# ble.net
KiCad netlist of a schematic drawn in EAGLE
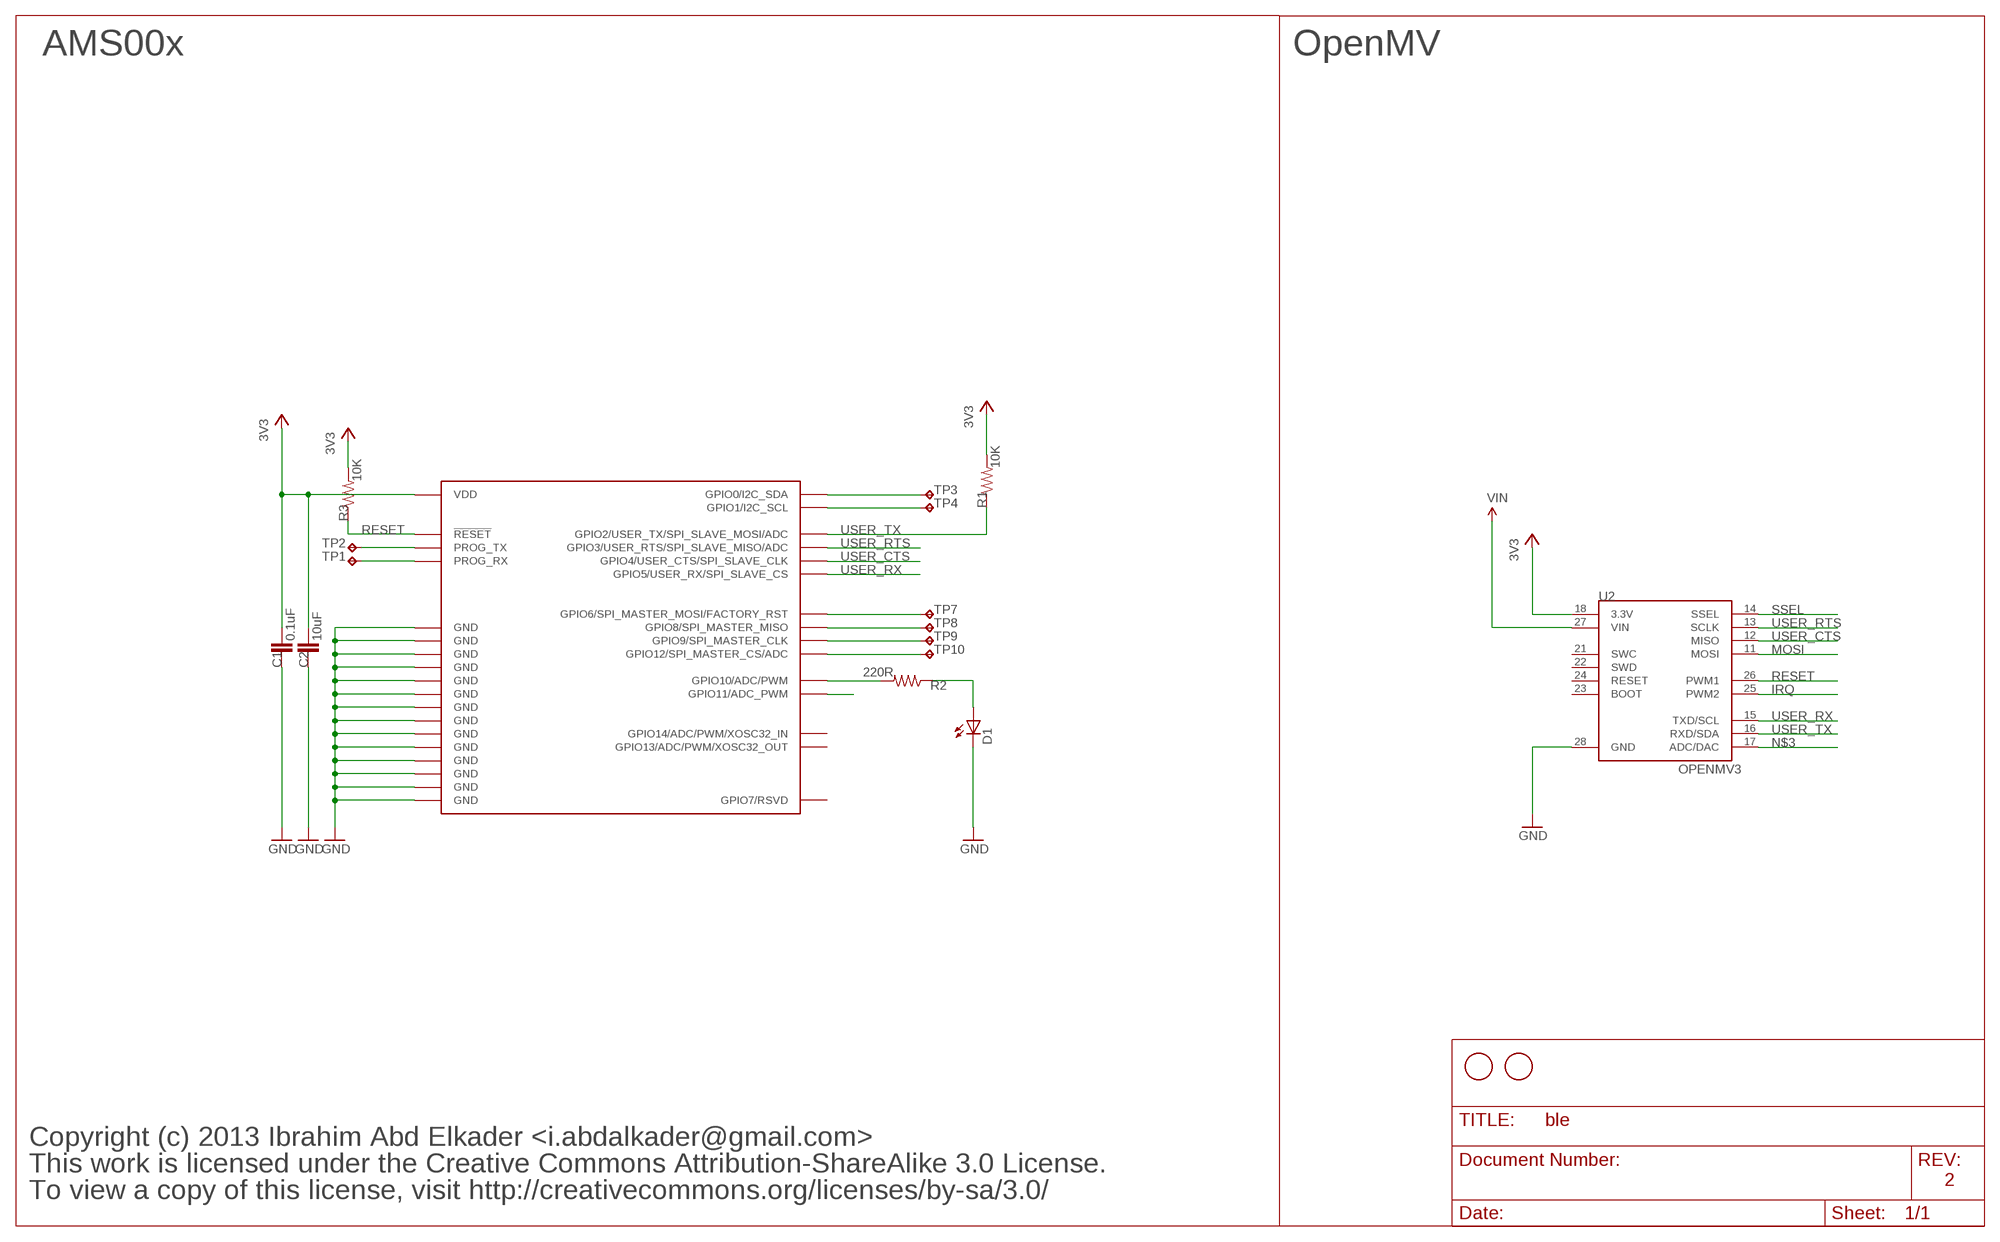
[diagram p0: schematic, sheet 1]

(export (version "E")
  (design (tool "Eeschema 10.0.6"))
  (components
    (comp (ref "C1")
      (value "0.1uF")
      (footprint "eagle-import:0603-CAP")
      (libsource (lib "eagle-import") (part "CAP0603-CAP"))
    )
    (comp (ref "C2")
      (value "10uF")
      (footprint "eagle-import:0805")
      (libsource (lib "eagle-import") (part "CAP0805"))
    )
    (comp (ref "D1")
      (value "LED0603")
      (footprint "eagle-import:LED-0603")
      (libsource (lib "eagle-import") (part "LED0603"))
    )
    (comp (ref "R1")
      (value "10K")
      (footprint "eagle-import:0603-RES")
      (libsource (lib "eagle-import") (part "RESISTOR0603-RES"))
    )
    (comp (ref "R2")
      (value "220R")
      (footprint "eagle-import:0603-RES")
      (libsource (lib "eagle-import") (part "RESISTOR0603-RES"))
    )
    (comp (ref "R3")
      (value "10K")
      (footprint "eagle-import:0603-RES")
      (libsource (lib "eagle-import") (part "RESISTOR0603-RES"))
    )
    (comp (ref "TP1")
      (value "TPTP12R")
      (footprint "eagle-import:TP12R")
      (libsource (lib "eagle-import") (part "TPTP12R"))
    )
    (comp (ref "TP2")
      (value "TPTP12R")
      (footprint "eagle-import:TP12R")
      (libsource (lib "eagle-import") (part "TPTP12R"))
    )
    (comp (ref "TP3")
      (value "TPTP12R")
      (footprint "eagle-import:TP12R")
      (libsource (lib "eagle-import") (part "TPTP12R"))
    )
    (comp (ref "TP4")
      (value "TPTP12R")
      (footprint "eagle-import:TP12R")
      (libsource (lib "eagle-import") (part "TPTP12R"))
    )
    (comp (ref "TP7")
      (value "TPTP12R")
      (footprint "eagle-import:TP12R")
      (libsource (lib "eagle-import") (part "TPTP12R"))
    )
    (comp (ref "TP8")
      (value "TPTP12R")
      (footprint "eagle-import:TP12R")
      (libsource (lib "eagle-import") (part "TPTP12R"))
    )
    (comp (ref "TP9")
      (value "TPTP12R")
      (footprint "eagle-import:TP12R")
      (libsource (lib "eagle-import") (part "TPTP12R"))
    )
    (comp (ref "TP10")
      (value "TPTP12R")
      (footprint "eagle-import:TP12R")
      (libsource (lib "eagle-import") (part "TPTP12R"))
    )
    (comp (ref "U$1")
      (value "FIDUCIAL")
      (footprint "eagle-import:FIDUCIAL_1MM")
      (libsource (lib "eagle-import") (part "FIDUCIAL"))
    )
    (comp (ref "U$2")
      (value "FIDUCIAL")
      (footprint "eagle-import:FIDUCIAL_1MM")
      (libsource (lib "eagle-import") (part "FIDUCIAL"))
    )
    (comp (ref "U$3")
      (value "AMS00X")
      (footprint "eagle-import:AMS00X")
      (libsource (lib "eagle-import") (part "AMS00X"))
    )
    (comp (ref "U2")
      (value "OPENMV3")
      (footprint "eagle-import:OPENMV3")
      (libsource (lib "eagle-import") (part "OPENMV3"))
    )
  )
  (nets
    (net (code "1") (name "/IRQ") (class "Default")
      (node (ref "U2") (pin "25") (pinfunction "PWM2_25") (pintype "bidirectional"))
    )
    (net (code "2") (name "/MOSI") (class "Default")
      (node (ref "U2") (pin "11") (pinfunction "MOSI_11") (pintype "bidirectional"))
    )
    (net (code "3") (name "/N$3") (class "Default")
      (node (ref "U2") (pin "17") (pinfunction "ADC/DAC_17") (pintype "bidirectional"))
    )
    (net (code "4") (name "/RESET") (class "Default")
      (node (ref "R3") (pin "1") (pinfunction "1_1") (pintype "passive"))
      (node (ref "U$3") (pin "P$8") (pinfunction "~{RESET}_P$8") (pintype "bidirectional"))
      (node (ref "U2") (pin "26") (pinfunction "PWM1_26") (pintype "bidirectional"))
    )
    (net (code "5") (name "/SSEL") (class "Default")
      (node (ref "U2") (pin "14") (pinfunction "SSEL_14") (pintype "bidirectional"))
    )
    (net (code "6") (name "/USER_CTS") (class "Default")
      (node (ref "U$3") (pin "P$9") (pinfunction "GPIO4/USER_CTS/SPI_SLAVE_CLK_P$9") (pintype "bidirectional"))
      (node (ref "U2") (pin "12") (pinfunction "MISO_12") (pintype "bidirectional"))
    )
    (net (code "7") (name "/USER_RTS") (class "Default")
      (node (ref "U$3") (pin "P$7") (pinfunction "GPIO3/USER_RTS/SPI_SLAVE_MISO/ADC_P$7") (pintype "bidirectional"))
      (node (ref "U2") (pin "13") (pinfunction "SCLK_13") (pintype "bidirectional"))
    )
    (net (code "8") (name "/USER_RX") (class "Default")
      (node (ref "U$3") (pin "P$10") (pinfunction "GPIO5/USER_RX/SPI_SLAVE_CS_P$10") (pintype "bidirectional"))
      (node (ref "U2") (pin "15") (pinfunction "TXD/SCL_15") (pintype "bidirectional"))
    )
    (net (code "9") (name "/USER_TX") (class "Default")
      (node (ref "R1") (pin "1") (pinfunction "1_1") (pintype "passive"))
      (node (ref "U$3") (pin "P$6") (pinfunction "GPIO2/USER_TX/SPI_SLAVE_MOSI/ADC_P$6") (pintype "bidirectional"))
      (node (ref "U2") (pin "16") (pinfunction "RXD/SDA_16") (pintype "bidirectional"))
    )
    (net (code "10") (name "3V3") (class "Default")
      (node (ref "C1") (pin "2") (pinfunction "2_2") (pintype "passive"))
      (node (ref "C2") (pin "2") (pinfunction "2_2") (pintype "passive"))
      (node (ref "R1") (pin "2") (pinfunction "2_2") (pintype "passive"))
      (node (ref "R3") (pin "2") (pinfunction "2_2") (pintype "passive"))
      (node (ref "U$3") (pin "P$21") (pinfunction "VDD_P$21") (pintype "power_in"))
      (node (ref "U2") (pin "18") (pinfunction "3.3V_18") (pintype "power_in"))
    )
    (net (code "11") (name "GND") (class "Default")
      (node (ref "C1") (pin "1") (pinfunction "1_1") (pintype "passive"))
      (node (ref "C2") (pin "1") (pinfunction "1_1") (pintype "passive"))
      (node (ref "D1") (pin "C") (pinfunction "C_C") (pintype "passive"))
      (node (ref "U$3") (pin "P$1") (pinfunction "GND_P$1") (pintype "power_in"))
      (node (ref "U$3") (pin "P$19") (pinfunction "GND_P$19") (pintype "power_in"))
      (node (ref "U$3") (pin "P$22") (pinfunction "GND_P$22") (pintype "power_in"))
      (node (ref "U$3") (pin "P$23") (pinfunction "GND_P$23") (pintype "power_in"))
      (node (ref "U$3") (pin "P$24") (pinfunction "GND_P$24") (pintype "power_in"))
      (node (ref "U$3") (pin "P$25") (pinfunction "GND_P$25") (pintype "power_in"))
      (node (ref "U$3") (pin "P$26") (pinfunction "GND_P$26") (pintype "power_in"))
      (node (ref "U$3") (pin "P$27") (pinfunction "GND_P$27") (pintype "power_in"))
      (node (ref "U$3") (pin "P$28") (pinfunction "GND_P$28") (pintype "power_in"))
      (node (ref "U$3") (pin "P$29") (pinfunction "GND_P$29") (pintype "power_in"))
      (node (ref "U$3") (pin "P$30") (pinfunction "GND_P$30") (pintype "power_in"))
      (node (ref "U$3") (pin "P$31") (pinfunction "GND_P$31") (pintype "power_in"))
      (node (ref "U$3") (pin "P$32") (pinfunction "GND_P$32") (pintype "power_in"))
      (node (ref "U$3") (pin "P$33") (pinfunction "GND_P$33") (pintype "power_in"))
      (node (ref "U2") (pin "28") (pinfunction "GND_28") (pintype "power_in"))
    )
    (net (code "12") (name "Net-(D1-PadA)") (class "Default")
      (node (ref "D1") (pin "A") (pinfunction "A_A") (pintype "passive"))
      (node (ref "R2") (pin "1") (pinfunction "1_1") (pintype "passive"))
    )
    (net (code "13") (name "Net-(U$3-GPIO0{slash}I2C_SDA)") (class "Default")
      (node (ref "TP3") (pin "TP") (pinfunction "TP_TP") (pintype "input"))
      (node (ref "U$3") (pin "P$4") (pinfunction "GPIO0/I2C_SDA_P$4") (pintype "bidirectional"))
    )
    (net (code "14") (name "Net-(U$3-GPIO1{slash}I2C_SCL)") (class "Default")
      (node (ref "TP4") (pin "TP") (pinfunction "TP_TP") (pintype "input"))
      (node (ref "U$3") (pin "P$5") (pinfunction "GPIO1/I2C_SCL_P$5") (pintype "bidirectional"))
    )
    (net (code "15") (name "Net-(U$3-GPIO6{slash}SPI_MASTER_MOSI{slash}FACTORY_RST)") (class "Default")
      (node (ref "TP7") (pin "TP") (pinfunction "TP_TP") (pintype "input"))
      (node (ref "U$3") (pin "P$11") (pinfunction "GPIO6/SPI_MASTER_MOSI/FACTORY_RST_P$11") (pintype "bidirectional"))
    )
    (net (code "16") (name "Net-(U$3-GPIO8{slash}SPI_MASTER_MISO)") (class "Default")
      (node (ref "TP8") (pin "TP") (pinfunction "TP_TP") (pintype "input"))
      (node (ref "U$3") (pin "P$13") (pinfunction "GPIO8/SPI_MASTER_MISO_P$13") (pintype "bidirectional"))
    )
    (net (code "17") (name "Net-(U$3-GPIO9{slash}SPI_MASTER_CLK)") (class "Default")
      (node (ref "TP9") (pin "TP") (pinfunction "TP_TP") (pintype "input"))
      (node (ref "U$3") (pin "P$14") (pinfunction "GPIO9/SPI_MASTER_CLK_P$14") (pintype "bidirectional"))
    )
    (net (code "18") (name "Net-(U$3-GPIO10{slash}ADC{slash}PWM)") (class "Default")
      (node (ref "R2") (pin "2") (pinfunction "2_2") (pintype "passive"))
      (node (ref "U$3") (pin "P$15") (pinfunction "GPIO10/ADC/PWM_P$15") (pintype "bidirectional"))
    )
    (net (code "19") (name "Net-(U$3-GPIO12{slash}SPI_MASTER_CS{slash}ADC)") (class "Default")
      (node (ref "TP10") (pin "TP") (pinfunction "TP_TP") (pintype "input"))
      (node (ref "U$3") (pin "P$17") (pinfunction "GPIO12/SPI_MASTER_CS/ADC_P$17") (pintype "bidirectional"))
    )
    (net (code "20") (name "Net-(U$3-PROG_RX)") (class "Default")
      (node (ref "TP1") (pin "TP") (pinfunction "TP_TP") (pintype "input"))
      (node (ref "U$3") (pin "P$2") (pinfunction "PROG_RX_P$2") (pintype "bidirectional"))
    )
    (net (code "21") (name "Net-(U$3-PROG_TX)") (class "Default")
      (node (ref "TP2") (pin "TP") (pinfunction "TP_TP") (pintype "input"))
      (node (ref "U$3") (pin "P$3") (pinfunction "PROG_TX_P$3") (pintype "bidirectional"))
    )
    (net (code "22") (name "VIN") (class "Default")
      (node (ref "U2") (pin "27") (pinfunction "VIN_27") (pintype "power_in"))
    )
    (net (code "23") (name "unconnected-(U$3-GPIO7{slash}RSVD-PadP$12)") (class "Default")
      (node (ref "U$3") (pin "P$12") (pinfunction "GPIO7/RSVD_P$12") (pintype "no_connect"))
    )
    (net (code "24") (name "unconnected-(U$3-GPIO11{slash}ADC_PWM-PadP$16)") (class "Default")
      (node (ref "U$3") (pin "P$16") (pinfunction "GPIO11/ADC_PWM_P$16") (pintype "bidirectional"))
    )
    (net (code "25") (name "unconnected-(U$3-GPIO13{slash}ADC{slash}PWM{slash}XOSC32_OUT-PadP$18)") (class "Default")
      (node (ref "U$3") (pin "P$18") (pinfunction "GPIO13/ADC/PWM/XOSC32_OUT_P$18") (pintype "bidirectional"))
    )
    (net (code "26") (name "unconnected-(U$3-GPIO14{slash}ADC{slash}PWM{slash}XOSC32_IN-PadP$20)") (class "Default")
      (node (ref "U$3") (pin "P$20") (pinfunction "GPIO14/ADC/PWM/XOSC32_IN_P$20") (pintype "bidirectional"))
    )
    (net (code "27") (name "unconnected-(U2-BOOT-Pad23)") (class "Default")
      (node (ref "U2") (pin "23") (pinfunction "BOOT_23") (pintype "bidirectional"))
    )
    (net (code "28") (name "unconnected-(U2-RESET-Pad24)") (class "Default")
      (node (ref "U2") (pin "24") (pinfunction "RESET_24") (pintype "bidirectional"))
    )
    (net (code "29") (name "unconnected-(U2-SWC-Pad21)") (class "Default")
      (node (ref "U2") (pin "21") (pinfunction "SWC_21") (pintype "bidirectional"))
    )
    (net (code "30") (name "unconnected-(U2-SWD-Pad22)") (class "Default")
      (node (ref "U2") (pin "22") (pinfunction "SWD_22") (pintype "bidirectional"))
    )
  )
)
